# LGA-12.net
KiCad netlist of a schematic drawn in EAGLE
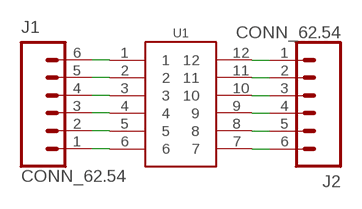
[diagram p0: schematic, sheet 1]

(export (version "E")
  (design (tool "Eeschema 10.0.6"))
  (components
    (comp (ref "J1")
      (value "CONN_62.54")
      (footprint "eagle-import:1X06")
      (libsource (lib "eagle-import") (part "CONN_62.54"))
    )
    (comp (ref "J2")
      (value "CONN_62.54")
      (footprint "eagle-import:1X06")
      (libsource (lib "eagle-import") (part "CONN_62.54"))
    )
    (comp (ref "U1")
      (value "GEN_12LGA12_2X2")
      (footprint "eagle-import:LGA-12_2X2")
      (libsource (lib "eagle-import") (part "GEN_12LGA12_2X2"))
    )
  )
  (nets
    (net (code "1") (name "Net-(J1-Pad1)") (class "Default")
      (node (ref "J1") (pin "1") (pinfunction "1_1") (pintype "passive"))
      (node (ref "U1") (pin "6") (pinfunction "6_6") (pintype "bidirectional"))
    )
    (net (code "2") (name "Net-(J1-Pad2)") (class "Default")
      (node (ref "J1") (pin "2") (pinfunction "2_2") (pintype "passive"))
      (node (ref "U1") (pin "5") (pinfunction "5_5") (pintype "bidirectional"))
    )
    (net (code "3") (name "Net-(J1-Pad3)") (class "Default")
      (node (ref "J1") (pin "3") (pinfunction "3_3") (pintype "passive"))
      (node (ref "U1") (pin "4") (pinfunction "4_4") (pintype "bidirectional"))
    )
    (net (code "4") (name "Net-(J1-Pad4)") (class "Default")
      (node (ref "J1") (pin "4") (pinfunction "4_4") (pintype "passive"))
      (node (ref "U1") (pin "3") (pinfunction "3_3") (pintype "bidirectional"))
    )
    (net (code "5") (name "Net-(J1-Pad5)") (class "Default")
      (node (ref "J1") (pin "5") (pinfunction "5_5") (pintype "passive"))
      (node (ref "U1") (pin "2") (pinfunction "2_2") (pintype "bidirectional"))
    )
    (net (code "6") (name "Net-(J1-Pad6)") (class "Default")
      (node (ref "J1") (pin "6") (pinfunction "6_6") (pintype "passive"))
      (node (ref "U1") (pin "1") (pinfunction "1_1") (pintype "bidirectional"))
    )
    (net (code "7") (name "Net-(J2-Pad1)") (class "Default")
      (node (ref "J2") (pin "1") (pinfunction "1_1") (pintype "passive"))
      (node (ref "U1") (pin "12") (pinfunction "12_12") (pintype "bidirectional"))
    )
    (net (code "8") (name "Net-(J2-Pad2)") (class "Default")
      (node (ref "J2") (pin "2") (pinfunction "2_2") (pintype "passive"))
      (node (ref "U1") (pin "11") (pinfunction "11_11") (pintype "bidirectional"))
    )
    (net (code "9") (name "Net-(J2-Pad3)") (class "Default")
      (node (ref "J2") (pin "3") (pinfunction "3_3") (pintype "passive"))
      (node (ref "U1") (pin "10") (pinfunction "10_10") (pintype "bidirectional"))
    )
    (net (code "10") (name "Net-(J2-Pad4)") (class "Default")
      (node (ref "J2") (pin "4") (pinfunction "4_4") (pintype "passive"))
      (node (ref "U1") (pin "9") (pinfunction "9_9") (pintype "bidirectional"))
    )
    (net (code "11") (name "Net-(J2-Pad5)") (class "Default")
      (node (ref "J2") (pin "5") (pinfunction "5_5") (pintype "passive"))
      (node (ref "U1") (pin "8") (pinfunction "8_8") (pintype "bidirectional"))
    )
    (net (code "12") (name "Net-(J2-Pad6)") (class "Default")
      (node (ref "J2") (pin "6") (pinfunction "6_6") (pintype "passive"))
      (node (ref "U1") (pin "7") (pinfunction "7_7") (pintype "bidirectional"))
    )
  )
)
